# Power.net
KiCad netlist of a schematic drawn in Altium Designer
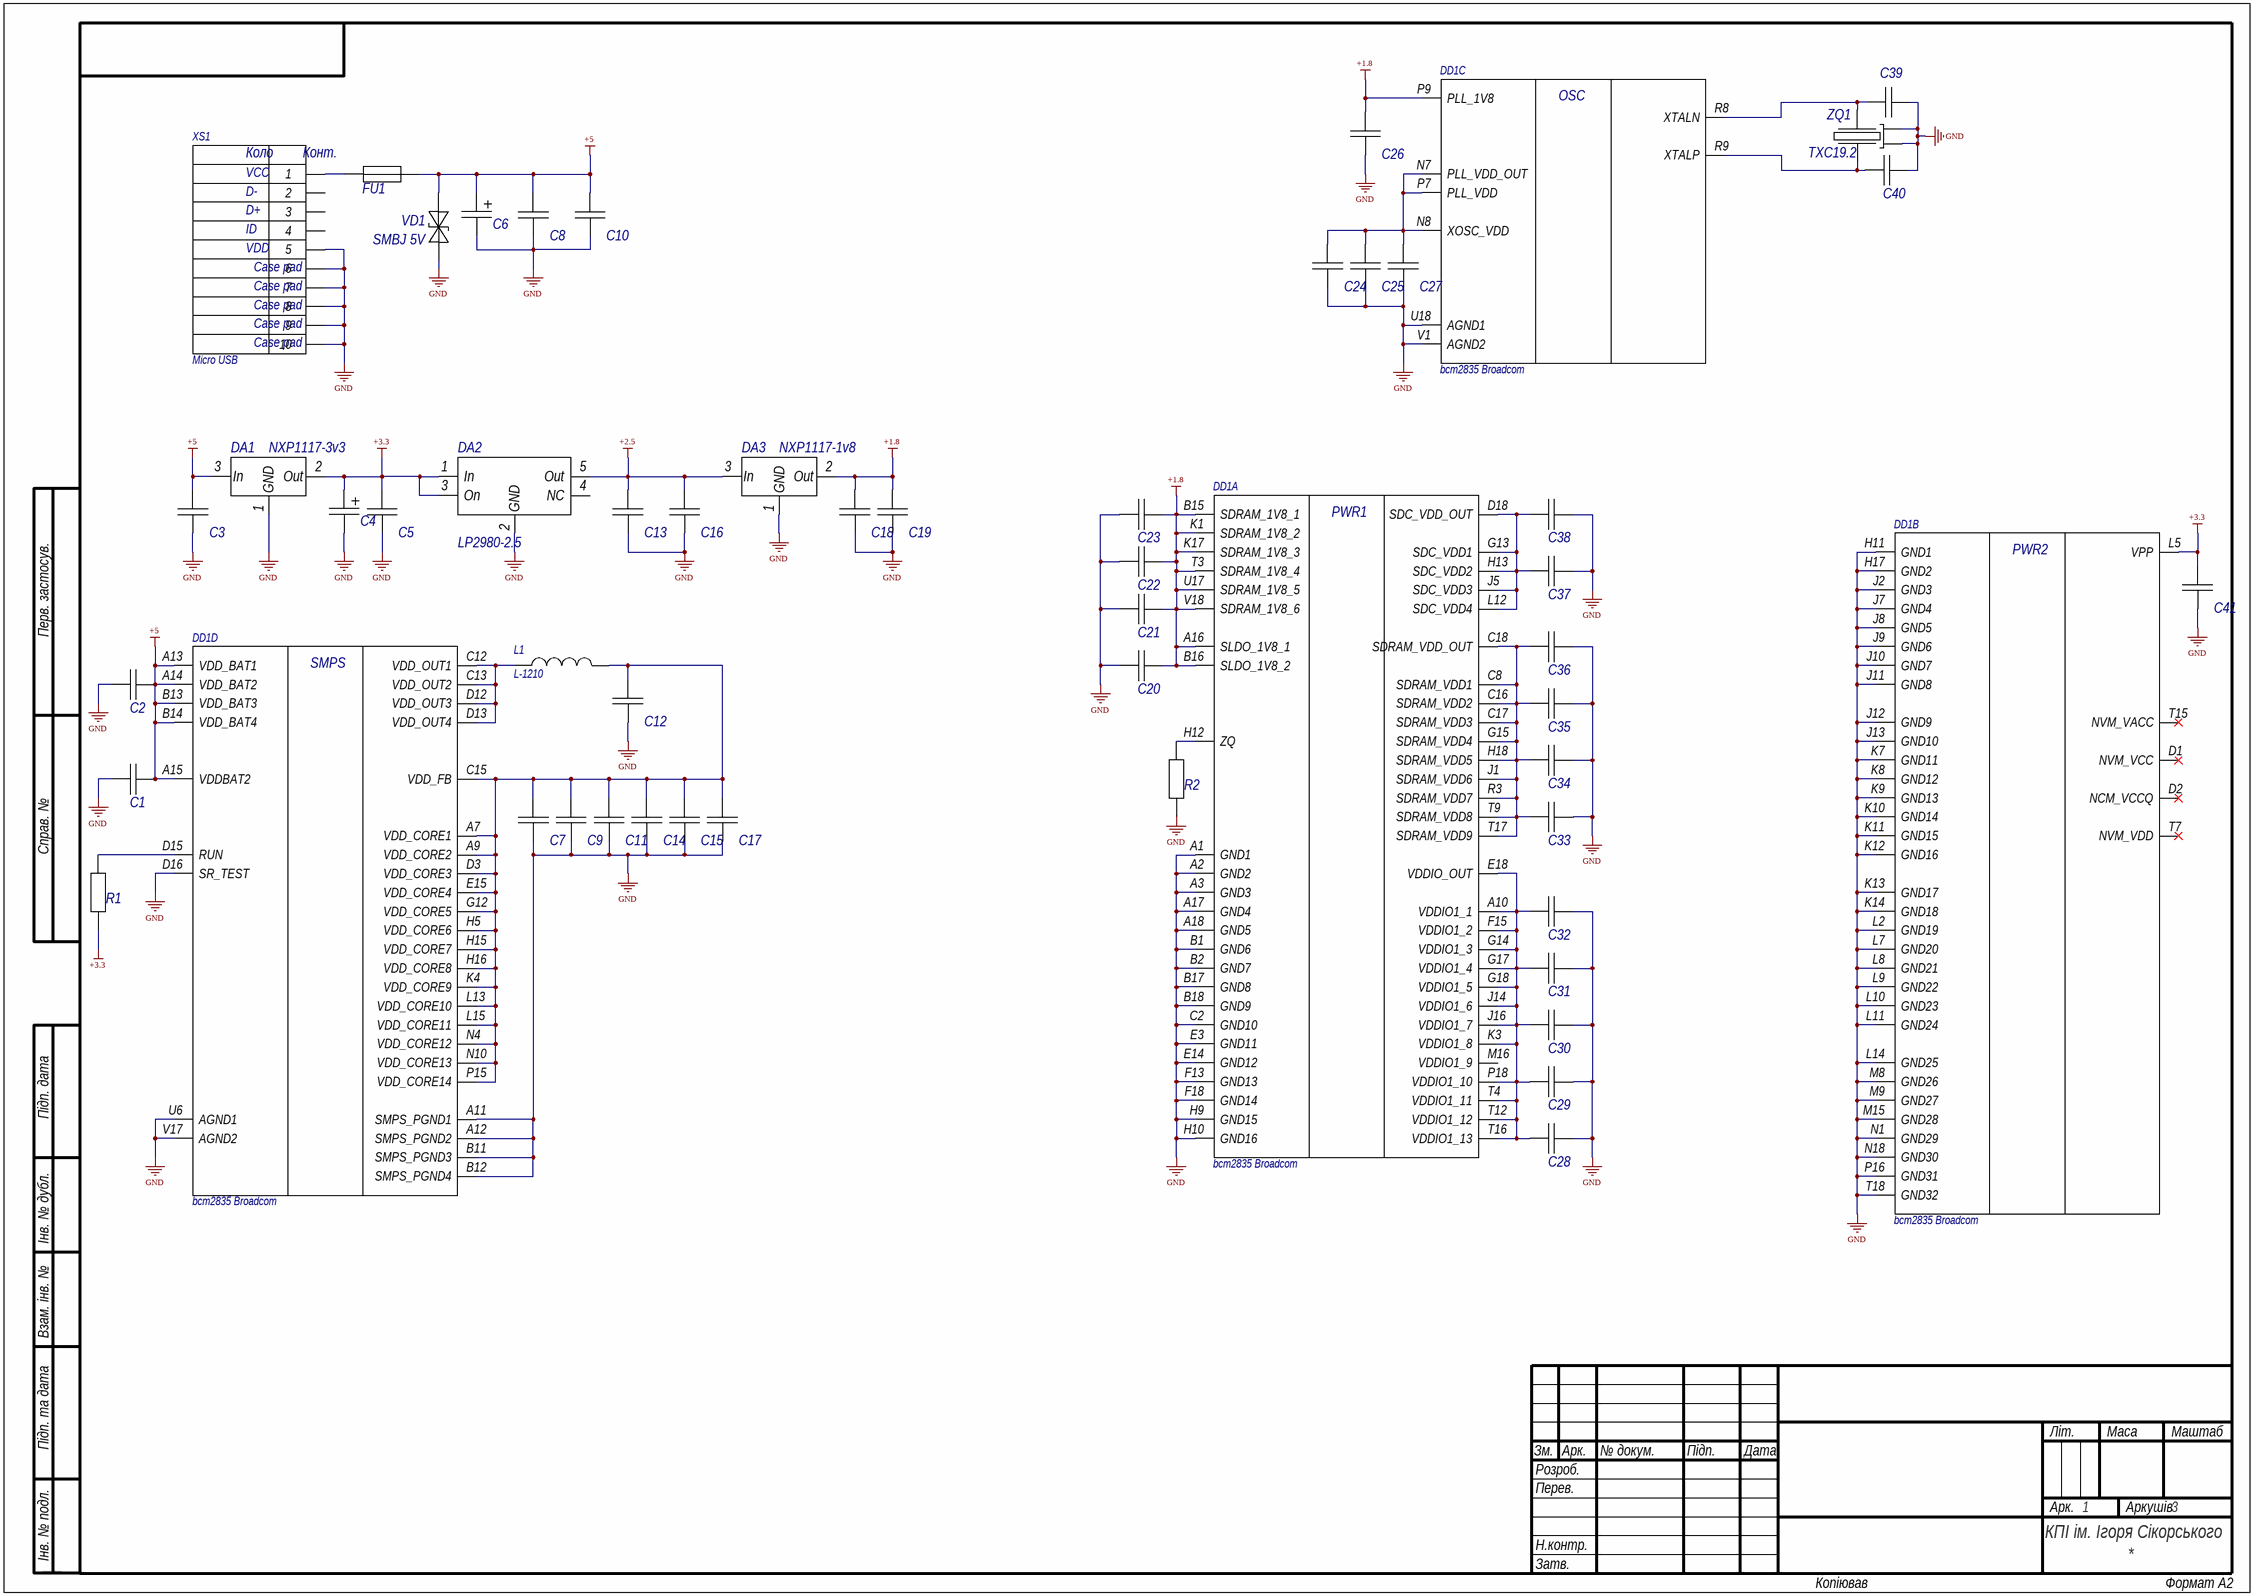
[diagram p0: Power.SchDoc]

(export (version "E")
  (design (tool "Eeschema 10.0.6"))
  (components
    (comp (ref "C1")
      (value "C-0603 * * * * *")
      (footprint "С-0603")
      (description "Generic")
      (libsource (lib "Schlib1") (part "С-0603"))
    )
    (comp (ref "C2")
      (value "C-0603 * * * * *")
      (footprint "С-0603")
      (description "Generic")
      (libsource (lib "Schlib1") (part "С-0603"))
    )
    (comp (ref "C3")
      (value "C-0805 * * * * *")
      (footprint "C-0805-KEM")
      (description "Generic")
      (libsource (lib "Schlib1") (part "С-0805"))
    )
    (comp (ref "C4")
      (value "C * * * * *")
      (footprint "PCAP_SVP_C6_PAN")
      (description "Generic electrolite SMT capacitor")
      (libsource (lib "Schlib1") (part "С"))
    )
    (comp (ref "C5")
      (value "C-0805 * * * * *")
      (footprint "C-0805-KEM")
      (description "Generic")
      (libsource (lib "Schlib1") (part "С-0805"))
    )
    (comp (ref "C6")
      (value "C * * * * *")
      (footprint "PCAP_SVP_C6_PAN")
      (description "Generic electrolite SMT capacitor")
      (libsource (lib "Schlib1") (part "С"))
    )
    (comp (ref "C7")
      (value "C-0603 * * * * *")
      (footprint "С-0603")
      (description "Generic")
      (libsource (lib "Schlib1") (part "С-0603"))
    )
    (comp (ref "C8")
      (value "C-1206 * * * * *")
      (footprint "C-1206")
      (description "Generic")
      (libsource (lib "Schlib1") (part "С-1206"))
    )
    (comp (ref "C9")
      (value "C-0603 * * * * *")
      (footprint "С-0603")
      (description "Generic")
      (libsource (lib "Schlib1") (part "С-0603"))
    )
    (comp (ref "C10")
      (value "C-0805 * * * * *")
      (footprint "C-0805-KEM")
      (description "Generic")
      (libsource (lib "Schlib1") (part "С-0805"))
    )
    (comp (ref "C11")
      (value "C-0603 * * * * *")
      (footprint "С-0603")
      (description "Generic")
      (libsource (lib "Schlib1") (part "С-0603"))
    )
    (comp (ref "C12")
      (value "C-1206 * * * * *")
      (footprint "C-1206")
      (description "Generic")
      (libsource (lib "Schlib1") (part "С-1206"))
    )
    (comp (ref "C13")
      (value "C-1206 * * * * *")
      (footprint "C-1206")
      (description "Generic")
      (libsource (lib "Schlib1") (part "С-1206"))
    )
    (comp (ref "C14")
      (value "C-0603 * * * * *")
      (footprint "С-0603")
      (description "Generic")
      (libsource (lib "Schlib1") (part "С-0603"))
    )
    (comp (ref "C15")
      (value "C-0603 * * * * *")
      (footprint "С-0603")
      (description "Generic")
      (libsource (lib "Schlib1") (part "С-0603"))
    )
    (comp (ref "C16")
      (value "C-0805 * * * * *")
      (footprint "C-0805-KEM")
      (description "Generic")
      (libsource (lib "Schlib1") (part "С-0805"))
    )
    (comp (ref "C17")
      (value "C-0603 * * * * *")
      (footprint "С-0603")
      (description "Generic")
      (libsource (lib "Schlib1") (part "С-0603"))
    )
    (comp (ref "C18")
      (value "C-0805 * * * * *")
      (footprint "C-0805-KEM")
      (description "Generic")
      (libsource (lib "Schlib1") (part "С-0805"))
    )
    (comp (ref "C19")
      (value "C-0603 * * * * *")
      (footprint "С-0603")
      (description "Generic")
      (libsource (lib "Schlib1") (part "С-0603"))
    )
    (comp (ref "C20")
      (value "C-0603 * * * * *")
      (footprint "С-0603")
      (description "Generic")
      (libsource (lib "Schlib1") (part "С-0603"))
    )
    (comp (ref "C21")
      (value "C-0603 * * * * *")
      (footprint "С-0603")
      (description "Generic")
      (libsource (lib "Schlib1") (part "С-0603"))
    )
    (comp (ref "C22")
      (value "C-0603 * * * * *")
      (footprint "С-0603")
      (description "Generic")
      (libsource (lib "Schlib1") (part "С-0603"))
    )
    (comp (ref "C23")
      (value "C-0603 * * * * *")
      (footprint "С-0603")
      (description "Generic")
      (libsource (lib "Schlib1") (part "С-0603"))
    )
    (comp (ref "C24")
      (value "C-0603 * * * * *")
      (footprint "С-0603")
      (description "Generic")
      (libsource (lib "Schlib1") (part "С-0603"))
    )
    (comp (ref "C25")
      (value "C-0603 * * * * *")
      (footprint "С-0603")
      (description "Generic")
      (libsource (lib "Schlib1") (part "С-0603"))
    )
    (comp (ref "C26")
      (value "C-0603 * * * * *")
      (footprint "С-0603")
      (description "Generic")
      (libsource (lib "Schlib1") (part "С-0603"))
    )
    (comp (ref "C27")
      (value "C-0603 * * * * *")
      (footprint "С-0603")
      (description "Generic")
      (libsource (lib "Schlib1") (part "С-0603"))
    )
    (comp (ref "C28")
      (value "C-0603 * * * * *")
      (footprint "С-0603")
      (description "Generic")
      (libsource (lib "Schlib1") (part "С-0603"))
    )
    (comp (ref "C29")
      (value "C-0603 * * * * *")
      (footprint "С-0603")
      (description "Generic")
      (libsource (lib "Schlib1") (part "С-0603"))
    )
    (comp (ref "C30")
      (value "C-0603 * * * * *")
      (footprint "С-0603")
      (description "Generic")
      (libsource (lib "Schlib1") (part "С-0603"))
    )
    (comp (ref "C31")
      (value "C-0603 * * * * *")
      (footprint "С-0603")
      (description "Generic")
      (libsource (lib "Schlib1") (part "С-0603"))
    )
    (comp (ref "C32")
      (value "C-0603 * * * * *")
      (footprint "С-0603")
      (description "Generic")
      (libsource (lib "Schlib1") (part "С-0603"))
    )
    (comp (ref "C33")
      (value "C-0603 * * * * *")
      (footprint "С-0603")
      (description "Generic")
      (libsource (lib "Schlib1") (part "С-0603"))
    )
    (comp (ref "C34")
      (value "C-0603 * * * * *")
      (footprint "С-0603")
      (description "Generic")
      (libsource (lib "Schlib1") (part "С-0603"))
    )
    (comp (ref "C35")
      (value "C-0603 * * * * *")
      (footprint "С-0603")
      (description "Generic")
      (libsource (lib "Schlib1") (part "С-0603"))
    )
    (comp (ref "C36")
      (value "C-0603 * * * * *")
      (footprint "С-0603")
      (description "Generic")
      (libsource (lib "Schlib1") (part "С-0603"))
    )
    (comp (ref "C37")
      (value "C-0603 * * * * *")
      (footprint "С-0603")
      (description "Generic")
      (libsource (lib "Schlib1") (part "С-0603"))
    )
    (comp (ref "C38")
      (value "C-0603 * * * * *")
      (footprint "С-0603")
      (description "Generic")
      (libsource (lib "Schlib1") (part "С-0603"))
    )
    (comp (ref "C39")
      (value "C-0402 * * * * *")
      (footprint "C-0402")
      (description "Generic")
      (libsource (lib "Schlib1") (part "С-0402"))
    )
    (comp (ref "C40")
      (value "C-0402 * * * * *")
      (footprint "C-0402")
      (description "Generic")
      (libsource (lib "Schlib1") (part "С-0402"))
    )
    (comp (ref "C41")
      (value "C-0603 * * * * *")
      (footprint "С-0603")
      (description "Generic")
      (libsource (lib "Schlib1") (part "С-0603"))
    )
    (comp (ref "DA1")
      (value "NXP1117-3v3")
      (footprint "D2PAK3_ONS")
      (description "LDO aat output 3.3V")
      (libsource (lib "Schlib1") (part "NXP1117-3v3"))
    )
    (comp (ref "DA2")
      (value "LP2980-2.5")
      (footprint "MF05A_TEX-L")
      (description "LDO at output 2.5V")
      (libsource (lib "Schlib1") (part "LP2980-2.5"))
    )
    (comp (ref "DA3")
      (value "NXP1117-1v8")
      (footprint "D2PAK3_ONS")
      (description "LDO aat output 1.8V")
      (libsource (lib "Schlib1") (part "NXP1117-1v8"))
    )
    (comp (ref "DD1")
      (value "bcm2835 Broadcom")
      (footprint "BGA81C65P18X18_1200X1200")
      (description "BCM2835 ARM-based processor")
      (fields (field (name "MANUFACTURER") "Broadcom"))
      (libsource (lib "Schlib1") (part "bcm2835"))
    )
    (comp (ref "FU1")
      (value "F-1206 * * * *")
      (footprint "FUSE_1206")
      (description "Generic Fuse 1206")
      (libsource (lib "Schlib1") (part "F-1206"))
    )
    (comp (ref "L1")
      (value "L-1210")
      (footprint "IND_NC_SUM")
      (description "Inductor")
      (libsource (lib "Schlib1") (part "L-1210"))
    )
    (comp (ref "R1")
      (value "R-0603 * * * *")
      (footprint "R-0603")
      (description "Generic")
      (libsource (lib "") (part "R-0603_1"))
    )
    (comp (ref "R2")
      (value "R-0603 * * * *")
      (footprint "R-0603")
      (description "Generic")
      (libsource (lib "Schlib1") (part "R-0603"))
    )
    (comp (ref "VD1")
      (value "SMBJ 5V *")
      (footprint "SMB_STM")
      (description "TVS 5V Diode")
      (fields (field (name "NAME") "SMBJ 5V"))
      (libsource (lib "Schlib1") (part "SMBJ 5V"))
    )
    (comp (ref "XS1")
      (value "Micro USB")
      (footprint "micro-usb")
      (description "Micro-USB connector for SMT mounting")
      (libsource (lib "Schlib1") (part "Micro-USB"))
    )
    (comp (ref "ZQ1")
      (value "TXC19.2 *")
      (footprint "CRYSTAL_TXC_7B")
      (description "TXC19.2 crystal 19.2 MHz")
      (fields (field (name "NAME") "TXC19.2"))
      (libsource (lib "Schlib1") (part "TXC19.2"))
    )
  )
  (nets
    (net (code "1") (name "+1.8") (class "Default")
      (node (ref "C18") (pin "2") (pinfunction "2_2") (pintype "passive"))
      (node (ref "C19") (pin "2") (pinfunction "2_2") (pintype "passive"))
      (node (ref "C20") (pin "2") (pinfunction "2_2") (pintype "passive"))
      (node (ref "C21") (pin "2") (pinfunction "2_2") (pintype "passive"))
      (node (ref "C22") (pin "2") (pinfunction "2_2") (pintype "passive"))
      (node (ref "C23") (pin "2") (pinfunction "2_2") (pintype "passive"))
      (node (ref "C26") (pin "2") (pinfunction "2_2") (pintype "passive"))
      (node (ref "DA3") (pin "2") (pinfunction "Out_2") (pintype "passive"))
      (node (ref "DD1") (pin "A16") (pinfunction "SLDO_1V8_1_A16") (pintype "passive"))
      (node (ref "DD1") (pin "B15") (pinfunction "SDRAM_1V8_1_B15") (pintype "passive"))
      (node (ref "DD1") (pin "B16") (pinfunction "SLDO_1V8_2_B16") (pintype "passive"))
      (node (ref "DD1") (pin "K1") (pinfunction "SDRAM_1V8_2_K1") (pintype "passive"))
      (node (ref "DD1") (pin "K17") (pinfunction "SDRAM_1V8_3_K17") (pintype "passive"))
      (node (ref "DD1") (pin "P9") (pinfunction "PLL_1V8_P9") (pintype "passive"))
      (node (ref "DD1") (pin "T3") (pinfunction "SDRAM_1V8_4_T3") (pintype "passive"))
      (node (ref "DD1") (pin "U17") (pinfunction "SDRAM_1V8_5_U17") (pintype "passive"))
      (node (ref "DD1") (pin "V18") (pinfunction "SDRAM_1V8_6_V18") (pintype "passive"))
    )
    (net (code "2") (name "+2.5") (class "Default")
      (node (ref "C13") (pin "2") (pinfunction "2_2") (pintype "passive"))
      (node (ref "C16") (pin "2") (pinfunction "2_2") (pintype "passive"))
      (node (ref "DA2") (pin "5") (pinfunction "Out_5") (pintype "passive"))
      (node (ref "DA3") (pin "3") (pinfunction "In_3") (pintype "passive"))
    )
    (net (code "3") (name "+3.3") (class "Default")
      (node (ref "C4") (pin "1") (pinfunction "1_1") (pintype "passive"))
      (node (ref "C41") (pin "2") (pinfunction "2_2") (pintype "passive"))
      (node (ref "C5") (pin "2") (pinfunction "2_2") (pintype "passive"))
      (node (ref "DA1") (pin "2") (pinfunction "Out_2") (pintype "passive"))
      (node (ref "DA2") (pin "1") (pinfunction "In_1") (pintype "passive"))
      (node (ref "DA2") (pin "3") (pinfunction "On_3") (pintype "passive"))
      (node (ref "DD1") (pin "L5") (pinfunction "VPP_L5") (pintype "passive"))
      (node (ref "R1") (pin "2") (pinfunction "2_2") (pintype "passive"))
    )
    (net (code "4") (name "+5") (class "Default")
      (node (ref "C1") (pin "1") (pinfunction "1_1") (pintype "passive"))
      (node (ref "C10") (pin "2") (pinfunction "2_2") (pintype "passive"))
      (node (ref "C2") (pin "1") (pinfunction "1_1") (pintype "passive"))
      (node (ref "C3") (pin "2") (pinfunction "2_2") (pintype "passive"))
      (node (ref "C6") (pin "1") (pinfunction "1_1") (pintype "passive"))
      (node (ref "C8") (pin "2") (pinfunction "2_2") (pintype "passive"))
      (node (ref "DA1") (pin "3") (pinfunction "In_3") (pintype "passive"))
      (node (ref "DD1") (pin "A13") (pinfunction "VDD_BAT1_A13") (pintype "passive"))
      (node (ref "DD1") (pin "A14") (pinfunction "VDD_BAT2_A14") (pintype "passive"))
      (node (ref "DD1") (pin "A15") (pinfunction "VDDBAT2_A15") (pintype "passive"))
      (node (ref "DD1") (pin "B13") (pinfunction "VDD_BAT3_B13") (pintype "passive"))
      (node (ref "DD1") (pin "B14") (pinfunction "VDD_BAT4_B14") (pintype "passive"))
      (node (ref "FU1") (pin "2") (pinfunction "2_2") (pintype "passive"))
      (node (ref "VD1") (pin "2") (pinfunction "2_2") (pintype "passive"))
    )
    (net (code "5") (name "GND") (class "Default")
      (node (ref "C1") (pin "2") (pinfunction "2_2") (pintype "passive"))
      (node (ref "C10") (pin "1") (pinfunction "1_1") (pintype "passive"))
      (node (ref "C11") (pin "1") (pinfunction "1_1") (pintype "passive"))
      (node (ref "C12") (pin "1") (pinfunction "1_1") (pintype "passive"))
      (node (ref "C13") (pin "1") (pinfunction "1_1") (pintype "passive"))
      (node (ref "C14") (pin "1") (pinfunction "1_1") (pintype "passive"))
      (node (ref "C15") (pin "1") (pinfunction "1_1") (pintype "passive"))
      (node (ref "C16") (pin "1") (pinfunction "1_1") (pintype "passive"))
      (node (ref "C17") (pin "1") (pinfunction "1_1") (pintype "passive"))
      (node (ref "C18") (pin "1") (pinfunction "1_1") (pintype "passive"))
      (node (ref "C19") (pin "1") (pinfunction "1_1") (pintype "passive"))
      (node (ref "C2") (pin "2") (pinfunction "2_2") (pintype "passive"))
      (node (ref "C20") (pin "1") (pinfunction "1_1") (pintype "passive"))
      (node (ref "C21") (pin "1") (pinfunction "1_1") (pintype "passive"))
      (node (ref "C22") (pin "1") (pinfunction "1_1") (pintype "passive"))
      (node (ref "C23") (pin "1") (pinfunction "1_1") (pintype "passive"))
      (node (ref "C24") (pin "1") (pinfunction "1_1") (pintype "passive"))
      (node (ref "C25") (pin "1") (pinfunction "1_1") (pintype "passive"))
      (node (ref "C26") (pin "1") (pinfunction "1_1") (pintype "passive"))
      (node (ref "C27") (pin "1") (pinfunction "1_1") (pintype "passive"))
      (node (ref "C28") (pin "1") (pinfunction "1_1") (pintype "passive"))
      (node (ref "C29") (pin "1") (pinfunction "1_1") (pintype "passive"))
      (node (ref "C3") (pin "1") (pinfunction "1_1") (pintype "passive"))
      (node (ref "C30") (pin "1") (pinfunction "1_1") (pintype "passive"))
      (node (ref "C31") (pin "1") (pinfunction "1_1") (pintype "passive"))
      (node (ref "C32") (pin "1") (pinfunction "1_1") (pintype "passive"))
      (node (ref "C33") (pin "1") (pinfunction "1_1") (pintype "passive"))
      (node (ref "C34") (pin "1") (pinfunction "1_1") (pintype "passive"))
      (node (ref "C35") (pin "1") (pinfunction "1_1") (pintype "passive"))
      (node (ref "C36") (pin "1") (pinfunction "1_1") (pintype "passive"))
      (node (ref "C37") (pin "1") (pinfunction "1_1") (pintype "passive"))
      (node (ref "C38") (pin "1") (pinfunction "1_1") (pintype "passive"))
      (node (ref "C39") (pin "2") (pinfunction "2_2") (pintype "passive"))
      (node (ref "C4") (pin "2") (pinfunction "2_2") (pintype "passive"))
      (node (ref "C40") (pin "2") (pinfunction "2_2") (pintype "passive"))
      (node (ref "C41") (pin "1") (pinfunction "1_1") (pintype "passive"))
      (node (ref "C5") (pin "1") (pinfunction "1_1") (pintype "passive"))
      (node (ref "C6") (pin "2") (pinfunction "2_2") (pintype "passive"))
      (node (ref "C7") (pin "1") (pinfunction "1_1") (pintype "passive"))
      (node (ref "C8") (pin "1") (pinfunction "1_1") (pintype "passive"))
      (node (ref "C9") (pin "1") (pinfunction "1_1") (pintype "passive"))
      (node (ref "DA1") (pin "1") (pinfunction "GND_1") (pintype "passive"))
      (node (ref "DA2") (pin "2") (pinfunction "GND_2") (pintype "passive"))
      (node (ref "DA3") (pin "1") (pinfunction "GND_1") (pintype "passive"))
      (node (ref "DD1") (pin "A1") (pinfunction "GND1_A1") (pintype "passive"))
      (node (ref "DD1") (pin "A11") (pinfunction "SMPS_PGND1_A11") (pintype "passive"))
      (node (ref "DD1") (pin "A12") (pinfunction "SMPS_PGND2_A12") (pintype "passive"))
      (node (ref "DD1") (pin "A17") (pinfunction "GND4_A17") (pintype "passive"))
      (node (ref "DD1") (pin "A18") (pinfunction "GND5_A18") (pintype "passive"))
      (node (ref "DD1") (pin "A2") (pinfunction "GND2_A2") (pintype "passive"))
      (node (ref "DD1") (pin "A3") (pinfunction "GND3_A3") (pintype "passive"))
      (node (ref "DD1") (pin "B1") (pinfunction "GND6_B1") (pintype "passive"))
      (node (ref "DD1") (pin "B11") (pinfunction "SMPS_PGND3_B11") (pintype "passive"))
      (node (ref "DD1") (pin "B12") (pinfunction "SMPS_PGND4_B12") (pintype "passive"))
      (node (ref "DD1") (pin "B17") (pinfunction "GND8_B17") (pintype "passive"))
      (node (ref "DD1") (pin "B18") (pinfunction "GND9_B18") (pintype "passive"))
      (node (ref "DD1") (pin "B2") (pinfunction "GND7_B2") (pintype "passive"))
      (node (ref "DD1") (pin "C2") (pinfunction "GND10_C2") (pintype "passive"))
      (node (ref "DD1") (pin "D16") (pinfunction "SR_TEST_D16") (pintype "passive"))
      (node (ref "DD1") (pin "E14") (pinfunction "GND12_E14") (pintype "passive"))
      (node (ref "DD1") (pin "E3") (pinfunction "GND11_E3") (pintype "passive"))
      (node (ref "DD1") (pin "F13") (pinfunction "GND13_F13") (pintype "passive"))
      (node (ref "DD1") (pin "F18") (pinfunction "GND14_F18") (pintype "passive"))
      (node (ref "DD1") (pin "H10") (pinfunction "GND16_H10") (pintype "passive"))
      (node (ref "DD1") (pin "H11") (pinfunction "GND1_H11") (pintype "passive"))
      (node (ref "DD1") (pin "H17") (pinfunction "GND2_H17") (pintype "passive"))
      (node (ref "DD1") (pin "H9") (pinfunction "GND15_H9") (pintype "passive"))
      (node (ref "DD1") (pin "J10") (pinfunction "GND7_J10") (pintype "passive"))
      (node (ref "DD1") (pin "J11") (pinfunction "GND8_J11") (pintype "passive"))
      (node (ref "DD1") (pin "J12") (pinfunction "GND9_J12") (pintype "passive"))
      (node (ref "DD1") (pin "J13") (pinfunction "GND10_J13") (pintype "passive"))
      (node (ref "DD1") (pin "J2") (pinfunction "GND3_J2") (pintype "passive"))
      (node (ref "DD1") (pin "J7") (pinfunction "GND4_J7") (pintype "passive"))
      (node (ref "DD1") (pin "J8") (pinfunction "GND5_J8") (pintype "passive"))
      (node (ref "DD1") (pin "J9") (pinfunction "GND6_J9") (pintype "passive"))
      (node (ref "DD1") (pin "K10") (pinfunction "GND14_K10") (pintype "passive"))
      (node (ref "DD1") (pin "K11") (pinfunction "GND15_K11") (pintype "passive"))
      (node (ref "DD1") (pin "K12") (pinfunction "GND16_K12") (pintype "passive"))
      (node (ref "DD1") (pin "K13") (pinfunction "GND17_K13") (pintype "passive"))
      (node (ref "DD1") (pin "K14") (pinfunction "GND18_K14") (pintype "passive"))
      (node (ref "DD1") (pin "K7") (pinfunction "GND11_K7") (pintype "passive"))
      (node (ref "DD1") (pin "K8") (pinfunction "GND12_K8") (pintype "passive"))
      (node (ref "DD1") (pin "K9") (pinfunction "GND13_K9") (pintype "passive"))
      (node (ref "DD1") (pin "L10") (pinfunction "GND23_L10") (pintype "passive"))
      (node (ref "DD1") (pin "L11") (pinfunction "GND24_L11") (pintype "passive"))
      (node (ref "DD1") (pin "L14") (pinfunction "GND25_L14") (pintype "passive"))
      (node (ref "DD1") (pin "L2") (pinfunction "GND19_L2") (pintype "passive"))
      (node (ref "DD1") (pin "L7") (pinfunction "GND20_L7") (pintype "passive"))
      (node (ref "DD1") (pin "L8") (pinfunction "GND21_L8") (pintype "passive"))
      (node (ref "DD1") (pin "L9") (pinfunction "GND22_L9") (pintype "passive"))
      (node (ref "DD1") (pin "M15") (pinfunction "GND28_M15") (pintype "passive"))
      (node (ref "DD1") (pin "M8") (pinfunction "GND26_M8") (pintype "passive"))
      (node (ref "DD1") (pin "M9") (pinfunction "GND27_M9") (pintype "passive"))
      (node (ref "DD1") (pin "N1") (pinfunction "GND29_N1") (pintype "passive"))
      (node (ref "DD1") (pin "N18") (pinfunction "GND30_N18") (pintype "passive"))
      (node (ref "DD1") (pin "P16") (pinfunction "GND31_P16") (pintype "passive"))
      (node (ref "DD1") (pin "T18") (pinfunction "GND32_T18") (pintype "passive"))
      (node (ref "DD1") (pin "U18") (pinfunction "AGND1_U18") (pintype "passive"))
      (node (ref "DD1") (pin "U6") (pinfunction "AGND1_U6") (pintype "passive"))
      (node (ref "DD1") (pin "V1") (pinfunction "AGND2_V1") (pintype "passive"))
      (node (ref "DD1") (pin "V17") (pinfunction "AGND2_V17") (pintype "passive"))
      (node (ref "R2") (pin "1") (pinfunction "1_1") (pintype "passive"))
      (node (ref "VD1") (pin "1") (pinfunction "1_1") (pintype "passive"))
      (node (ref "XS1") (pin "10") (pinfunction "10_10") (pintype "passive"))
      (node (ref "XS1") (pin "5") (pinfunction "5_5") (pintype "passive"))
      (node (ref "XS1") (pin "6") (pinfunction "6_6") (pintype "passive"))
      (node (ref "XS1") (pin "7") (pinfunction "7_7") (pintype "passive"))
      (node (ref "XS1") (pin "8") (pinfunction "8_8") (pintype "passive"))
      (node (ref "XS1") (pin "9") (pinfunction "9_9") (pintype "passive"))
      (node (ref "ZQ1") (pin "2") (pinfunction "2_2") (pintype "passive"))
      (node (ref "ZQ1") (pin "4") (pinfunction "4_4") (pintype "passive"))
    )
    (net (code "6") (name "Net-(DD1A-SDC_VDD1)") (class "Default")
      (node (ref "C37") (pin "2") (pinfunction "2_2") (pintype "passive"))
      (node (ref "C38") (pin "2") (pinfunction "2_2") (pintype "passive"))
      (node (ref "DD1") (pin "D18") (pinfunction "SDC_VDD_OUT_D18") (pintype "passive"))
      (node (ref "DD1") (pin "G13") (pinfunction "SDC_VDD1_G13") (pintype "passive"))
      (node (ref "DD1") (pin "H13") (pinfunction "SDC_VDD2_H13") (pintype "passive"))
      (node (ref "DD1") (pin "J5") (pinfunction "SDC_VDD3_J5") (pintype "passive"))
      (node (ref "DD1") (pin "L12") (pinfunction "SDC_VDD4_L12") (pintype "passive"))
    )
    (net (code "7") (name "Net-(DD1A-SDRAM_VDD1)") (class "Default")
      (node (ref "C33") (pin "2") (pinfunction "2_2") (pintype "passive"))
      (node (ref "C34") (pin "2") (pinfunction "2_2") (pintype "passive"))
      (node (ref "C35") (pin "2") (pinfunction "2_2") (pintype "passive"))
      (node (ref "C36") (pin "2") (pinfunction "2_2") (pintype "passive"))
      (node (ref "DD1") (pin "G15") (pinfunction "SDRAM_VDD4_G15") (pintype "passive"))
      (node (ref "DD1") (pin "H18") (pinfunction "SDRAM_VDD5_H18") (pintype "passive"))
      (node (ref "DD1") (pin "J1") (pinfunction "SDRAM_VDD6_J1") (pintype "passive"))
      (node (ref "DD1") (pin "R3") (pinfunction "SDRAM_VDD7_R3") (pintype "passive"))
      (node (ref "DD1") (pin "T17") (pinfunction "SDRAM_VDD9_T17") (pintype "passive"))
      (node (ref "DD1") (pin "T9") (pinfunction "SDRAM_VDD8_T9") (pintype "passive"))
      (node (ref "DD1") (pin "С16") (pinfunction "SDRAM_VDD2_С16") (pintype "passive"))
      (node (ref "DD1") (pin "С17") (pinfunction "SDRAM_VDD3_С17") (pintype "passive"))
      (node (ref "DD1") (pin "С18") (pinfunction "SDRAM_VDD_OUT_С18") (pintype "passive"))
      (node (ref "DD1") (pin "С8") (pinfunction "SDRAM_VDD1_С8") (pintype "passive"))
    )
    (net (code "8") (name "Net-(DD1A-VDDIO1_1)") (class "Default")
      (node (ref "C28") (pin "2") (pinfunction "2_2") (pintype "passive"))
      (node (ref "C29") (pin "2") (pinfunction "2_2") (pintype "passive"))
      (node (ref "C30") (pin "2") (pinfunction "2_2") (pintype "passive"))
      (node (ref "C31") (pin "2") (pinfunction "2_2") (pintype "passive"))
      (node (ref "C32") (pin "2") (pinfunction "2_2") (pintype "passive"))
      (node (ref "DD1") (pin "A10") (pinfunction "VDDIO1_1_A10") (pintype "passive"))
      (node (ref "DD1") (pin "E18") (pinfunction "VDDIO_OUT_E18") (pintype "passive"))
      (node (ref "DD1") (pin "F15") (pinfunction "VDDIO1_2_F15") (pintype "passive"))
      (node (ref "DD1") (pin "G14") (pinfunction "VDDIO1_3_G14") (pintype "passive"))
      (node (ref "DD1") (pin "G17") (pinfunction "VDDIO1_4_G17") (pintype "passive"))
      (node (ref "DD1") (pin "G18") (pinfunction "VDDIO1_5_G18") (pintype "passive"))
      (node (ref "DD1") (pin "J14") (pinfunction "VDDIO1_6_J14") (pintype "passive"))
      (node (ref "DD1") (pin "J16") (pinfunction "VDDIO1_7_J16") (pintype "passive"))
      (node (ref "DD1") (pin "K3") (pinfunction "VDDIO1_8_K3") (pintype "passive"))
      (node (ref "DD1") (pin "P18") (pinfunction "VDDIO1_10_P18") (pintype "passive"))
      (node (ref "DD1") (pin "T12") (pinfunction "VDDIO1_12_T12") (pintype "passive"))
      (node (ref "DD1") (pin "T16") (pinfunction "VDDIO1_13_T16") (pintype "passive"))
      (node (ref "DD1") (pin "T4") (pinfunction "VDDIO1_11_T4") (pintype "passive"))
    )
    (net (code "9") (name "Net-(DD1A-ZQ)") (class "Default")
      (node (ref "DD1") (pin "H12") (pinfunction "ZQ_H12") (pintype "passive"))
      (node (ref "R2") (pin "2") (pinfunction "2_2") (pintype "passive"))
    )
    (net (code "10") (name "Net-(DD1C-PLL_VDD)") (class "Default")
      (node (ref "C24") (pin "2") (pinfunction "2_2") (pintype "passive"))
      (node (ref "C25") (pin "2") (pinfunction "2_2") (pintype "passive"))
      (node (ref "C27") (pin "2") (pinfunction "2_2") (pintype "passive"))
      (node (ref "DD1") (pin "N7") (pinfunction "PLL_VDD_OUT_N7") (pintype "passive"))
      (node (ref "DD1") (pin "N8") (pinfunction "XOSC_VDD_N8") (pintype "passive"))
      (node (ref "DD1") (pin "P7") (pinfunction "PLL_VDD_P7") (pintype "passive"))
    )
    (net (code "11") (name "Net-(DD1C-XTALN)") (class "Default")
      (node (ref "C39") (pin "1") (pinfunction "1_1") (pintype "passive"))
      (node (ref "DD1") (pin "R8") (pinfunction "XTALN_R8") (pintype "passive"))
      (node (ref "ZQ1") (pin "3") (pinfunction "3_3") (pintype "passive"))
    )
    (net (code "12") (name "Net-(DD1C-XTALP)") (class "Default")
      (node (ref "C40") (pin "1") (pinfunction "1_1") (pintype "passive"))
      (node (ref "DD1") (pin "R9") (pinfunction "XTALP_R9") (pintype "passive"))
      (node (ref "ZQ1") (pin "1") (pinfunction "1_1") (pintype "passive"))
    )
    (net (code "13") (name "Net-(DD1D-RUN)") (class "Default")
      (node (ref "DD1") (pin "D15") (pinfunction "RUN_D15") (pintype "passive"))
      (node (ref "R1") (pin "1") (pinfunction "1_1") (pintype "passive"))
    )
    (net (code "14") (name "Net-(DD1D-VDD_CORE1)") (class "Default")
      (node (ref "C11") (pin "2") (pinfunction "2_2") (pintype "passive"))
      (node (ref "C12") (pin "2") (pinfunction "2_2") (pintype "passive"))
      (node (ref "C14") (pin "2") (pinfunction "2_2") (pintype "passive"))
      (node (ref "C15") (pin "2") (pinfunction "2_2") (pintype "passive"))
      (node (ref "C17") (pin "2") (pinfunction "2_2") (pintype "passive"))
      (node (ref "C7") (pin "2") (pinfunction "2_2") (pintype "passive"))
      (node (ref "C9") (pin "2") (pinfunction "2_2") (pintype "passive"))
      (node (ref "DD1") (pin "A7") (pinfunction "VDD_CORE1_A7") (pintype "passive"))
      (node (ref "DD1") (pin "A9") (pinfunction "VDD_CORE2_A9") (pintype "passive"))
      (node (ref "DD1") (pin "C15") (pinfunction "VDD_FB_C15") (pintype "passive"))
      (node (ref "DD1") (pin "D3") (pinfunction "VDD_CORE3_D3") (pintype "passive"))
      (node (ref "DD1") (pin "E15") (pinfunction "VDD_CORE4_E15") (pintype "passive"))
      (node (ref "DD1") (pin "G12") (pinfunction "VDD_CORE5_G12") (pintype "passive"))
      (node (ref "DD1") (pin "H15") (pinfunction "VDD_CORE7_H15") (pintype "passive"))
      (node (ref "DD1") (pin "H16") (pinfunction "VDD_CORE8_H16") (pintype "passive"))
      (node (ref "DD1") (pin "H5") (pinfunction "VDD_CORE6_H5") (pintype "passive"))
      (node (ref "DD1") (pin "K4") (pinfunction "VDD_CORE9_K4") (pintype "passive"))
      (node (ref "DD1") (pin "L13") (pinfunction "VDD_CORE10_L13") (pintype "passive"))
      (node (ref "DD1") (pin "L15") (pinfunction "VDD_CORE11_L15") (pintype "passive"))
      (node (ref "DD1") (pin "N10") (pinfunction "VDD_CORE13_N10") (pintype "passive"))
      (node (ref "DD1") (pin "N4") (pinfunction "VDD_CORE12_N4") (pintype "passive"))
      (node (ref "DD1") (pin "P15") (pinfunction "VDD_CORE14_P15") (pintype "passive"))
      (node (ref "L1") (pin "2") (pinfunction "2_2") (pintype "passive"))
    )
    (net (code "15") (name "Net-(DD1D-VDD_OUT1)") (class "Default")
      (node (ref "DD1") (pin "C12") (pinfunction "VDD_OUT1_C12") (pintype "passive"))
      (node (ref "DD1") (pin "C13") (pinfunction "VDD_OUT2_C13") (pintype "passive"))
      (node (ref "DD1") (pin "D12") (pinfunction "VDD_OUT3_D12") (pintype "passive"))
      (node (ref "DD1") (pin "D13") (pinfunction "VDD_OUT4_D13") (pintype "passive"))
      (node (ref "L1") (pin "1") (pinfunction "1_1") (pintype "passive"))
    )
    (net (code "16") (name "Net-(FU1-Pad1)") (class "Default")
      (node (ref "FU1") (pin "1") (pinfunction "1_1") (pintype "passive"))
      (node (ref "XS1") (pin "1") (pinfunction "1_1") (pintype "passive"))
    )
    (net (code "17") (name "unconnected-(DA2-NC-Pad4)") (class "Default")
      (node (ref "DA2") (pin "4") (pinfunction "NC_4") (pintype "passive"))
    )
    (net (code "18") (name "unconnected-(DD1A-VDDIO1_9-PadM16)") (class "Default")
      (node (ref "DD1") (pin "M16") (pinfunction "VDDIO1_9_M16") (pintype "passive"))
    )
    (net (code "19") (name "unconnected-(DD1B-NCM_VCCQ-PadD2)") (class "Default")
      (node (ref "DD1") (pin "D2") (pinfunction "NCM_VCCQ_D2") (pintype "passive+no_connect"))
    )
    (net (code "20") (name "unconnected-(DD1B-NVM_VACC-PadT15)") (class "Default")
      (node (ref "DD1") (pin "T15") (pinfunction "NVM_VACC_T15") (pintype "passive+no_connect"))
    )
    (net (code "21") (name "unconnected-(DD1B-NVM_VCC-PadD1)") (class "Default")
      (node (ref "DD1") (pin "D1") (pinfunction "NVM_VCC_D1") (pintype "passive+no_connect"))
    )
    (net (code "22") (name "unconnected-(DD1B-NVM_VDD-PadT7)") (class "Default")
      (node (ref "DD1") (pin "T7") (pinfunction "NVM_VDD_T7") (pintype "passive+no_connect"))
    )
    (net (code "23") (name "unconnected-(XS1-Pad2)") (class "Default")
      (node (ref "XS1") (pin "2") (pinfunction "2_2") (pintype "passive"))
    )
    (net (code "24") (name "unconnected-(XS1-Pad3)") (class "Default")
      (node (ref "XS1") (pin "3") (pinfunction "3_3") (pintype "passive"))
    )
    (net (code "25") (name "unconnected-(XS1-Pad4)") (class "Default")
      (node (ref "XS1") (pin "4") (pinfunction "4_4") (pintype "passive"))
    )
  )
)
